# fullerton.net
KiCad netlist of a schematic drawn in EAGLE
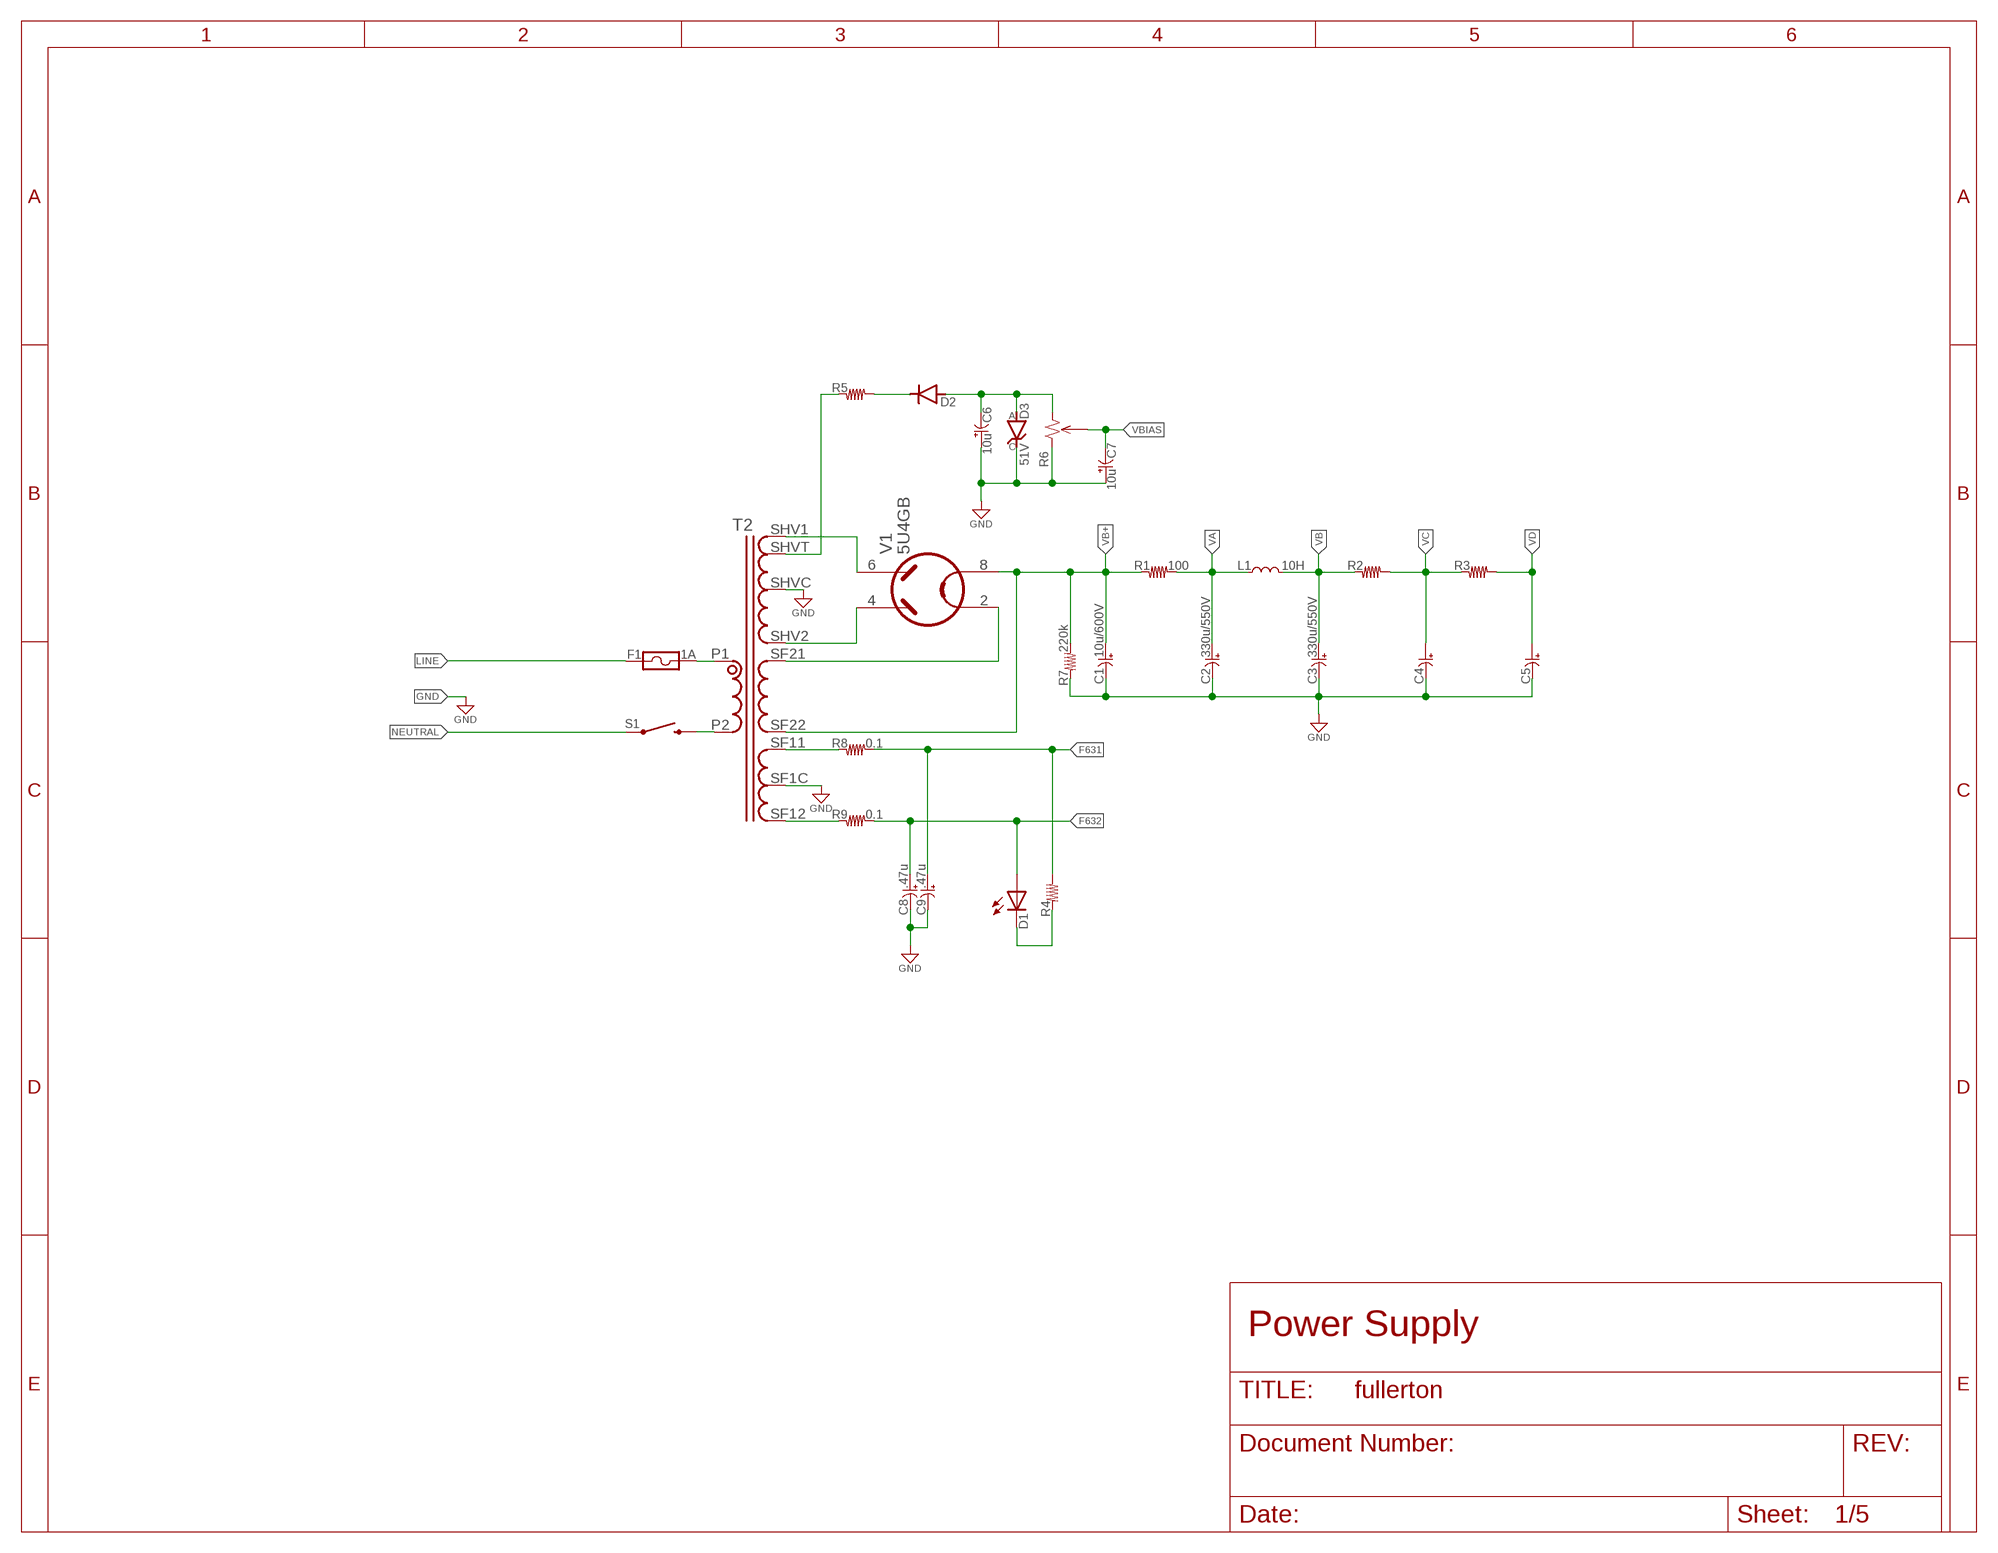
[diagram p0: schematic, sheet 1]
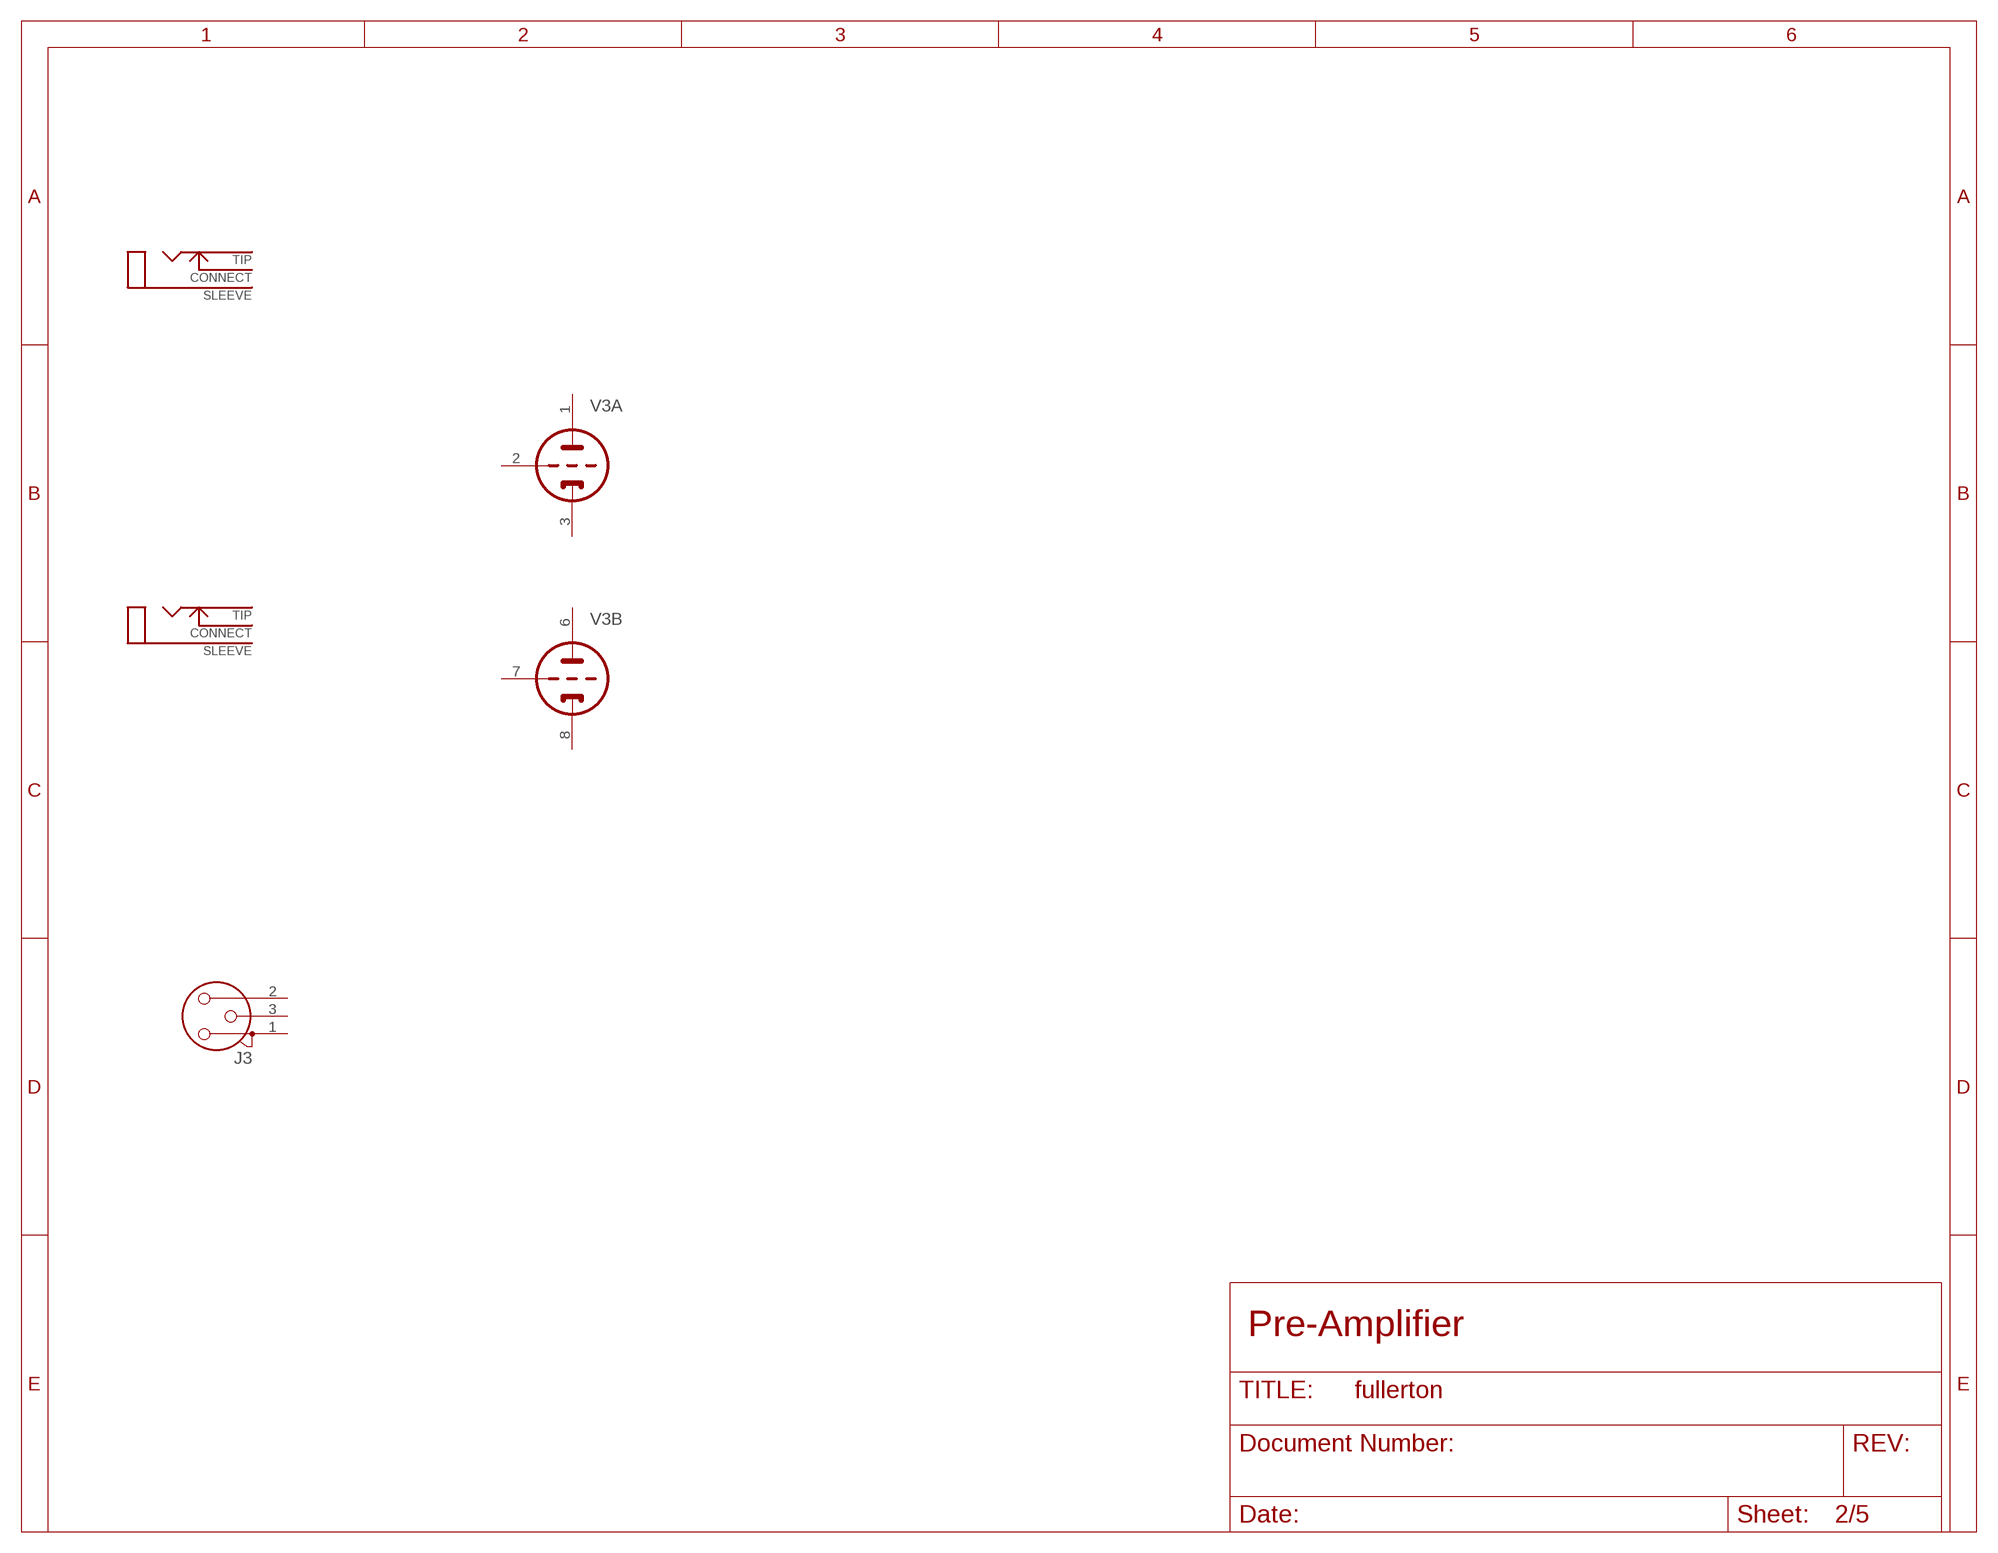
[diagram p1: schematic, sheet 2]
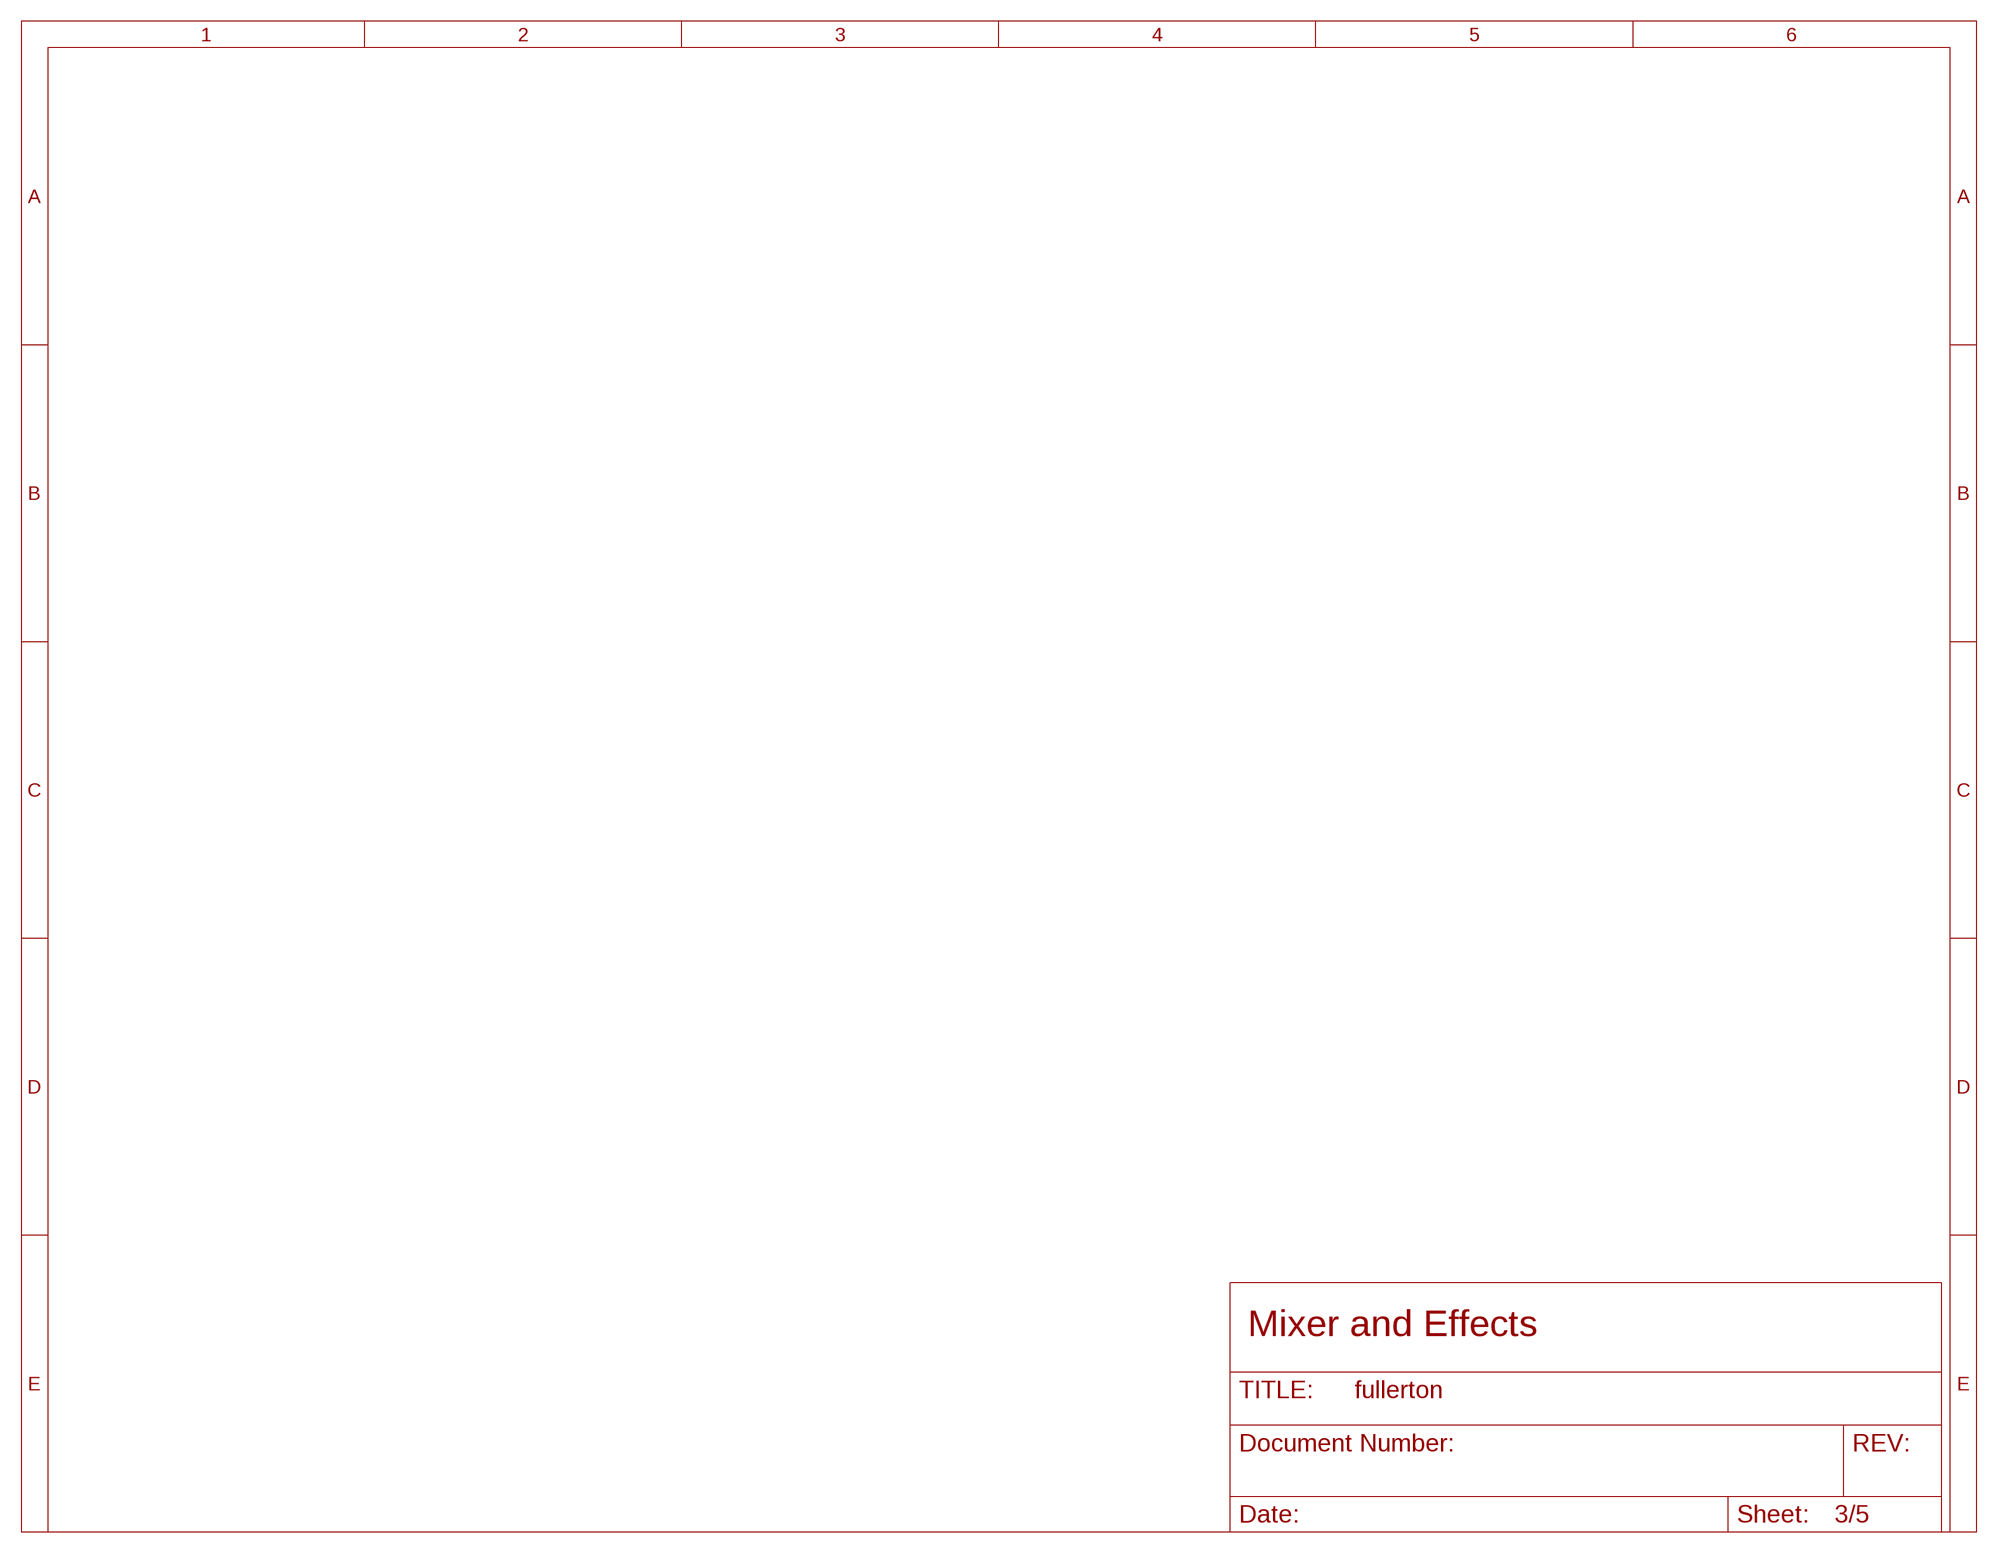
[diagram p2: schematic, sheet 3]
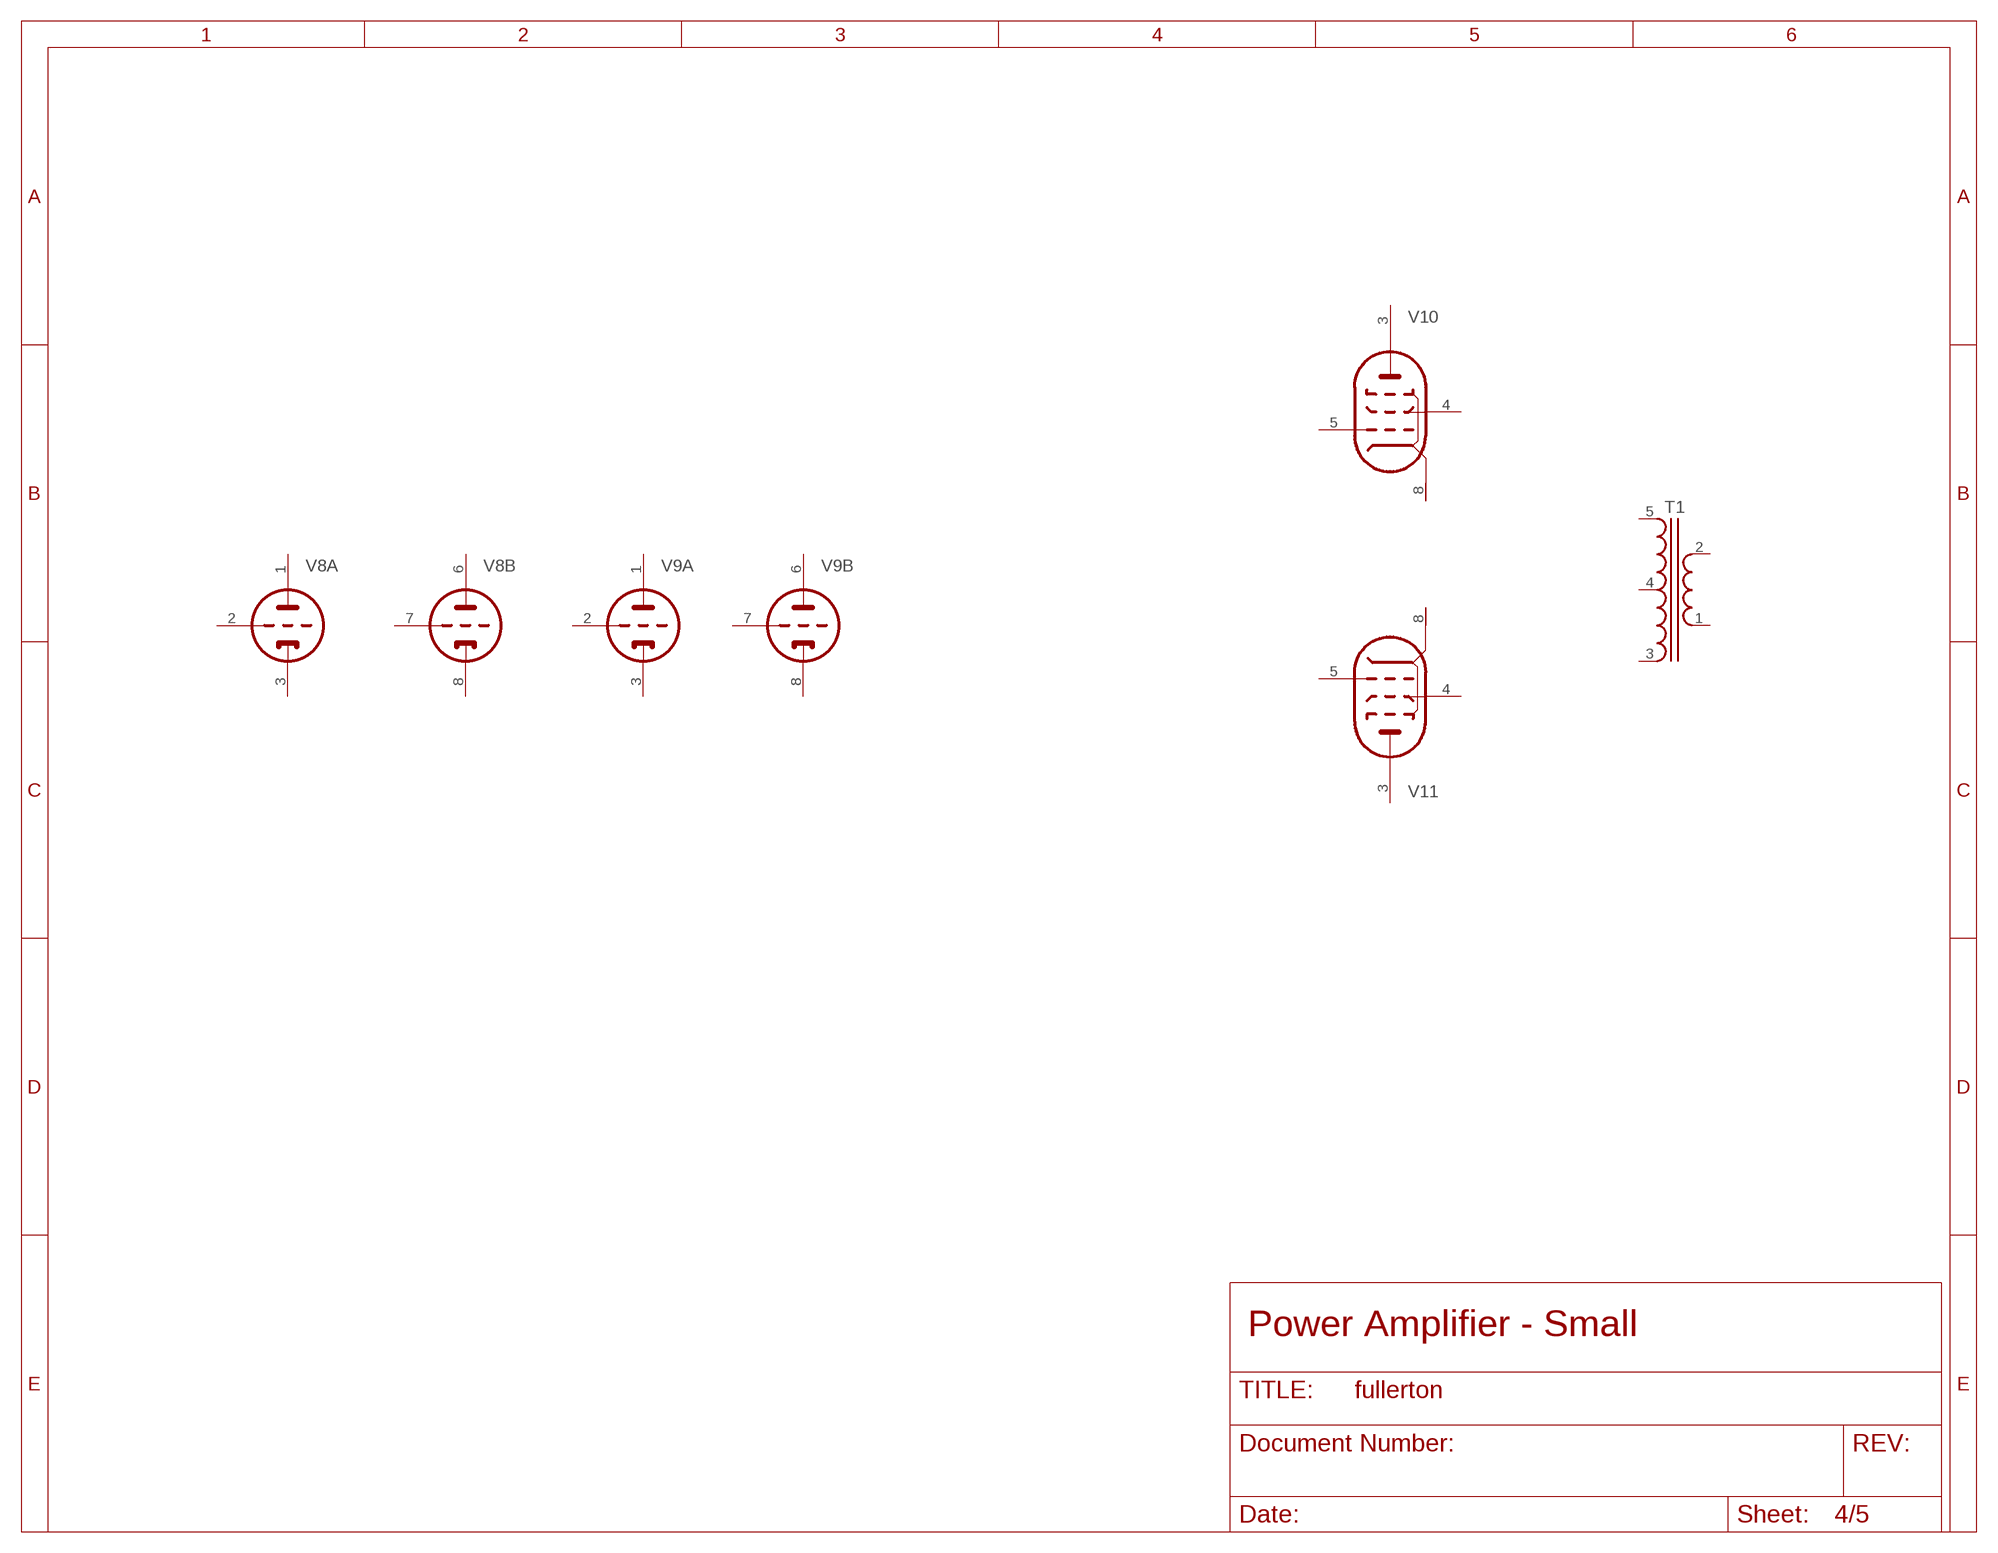
[diagram p3: schematic, sheet 4]
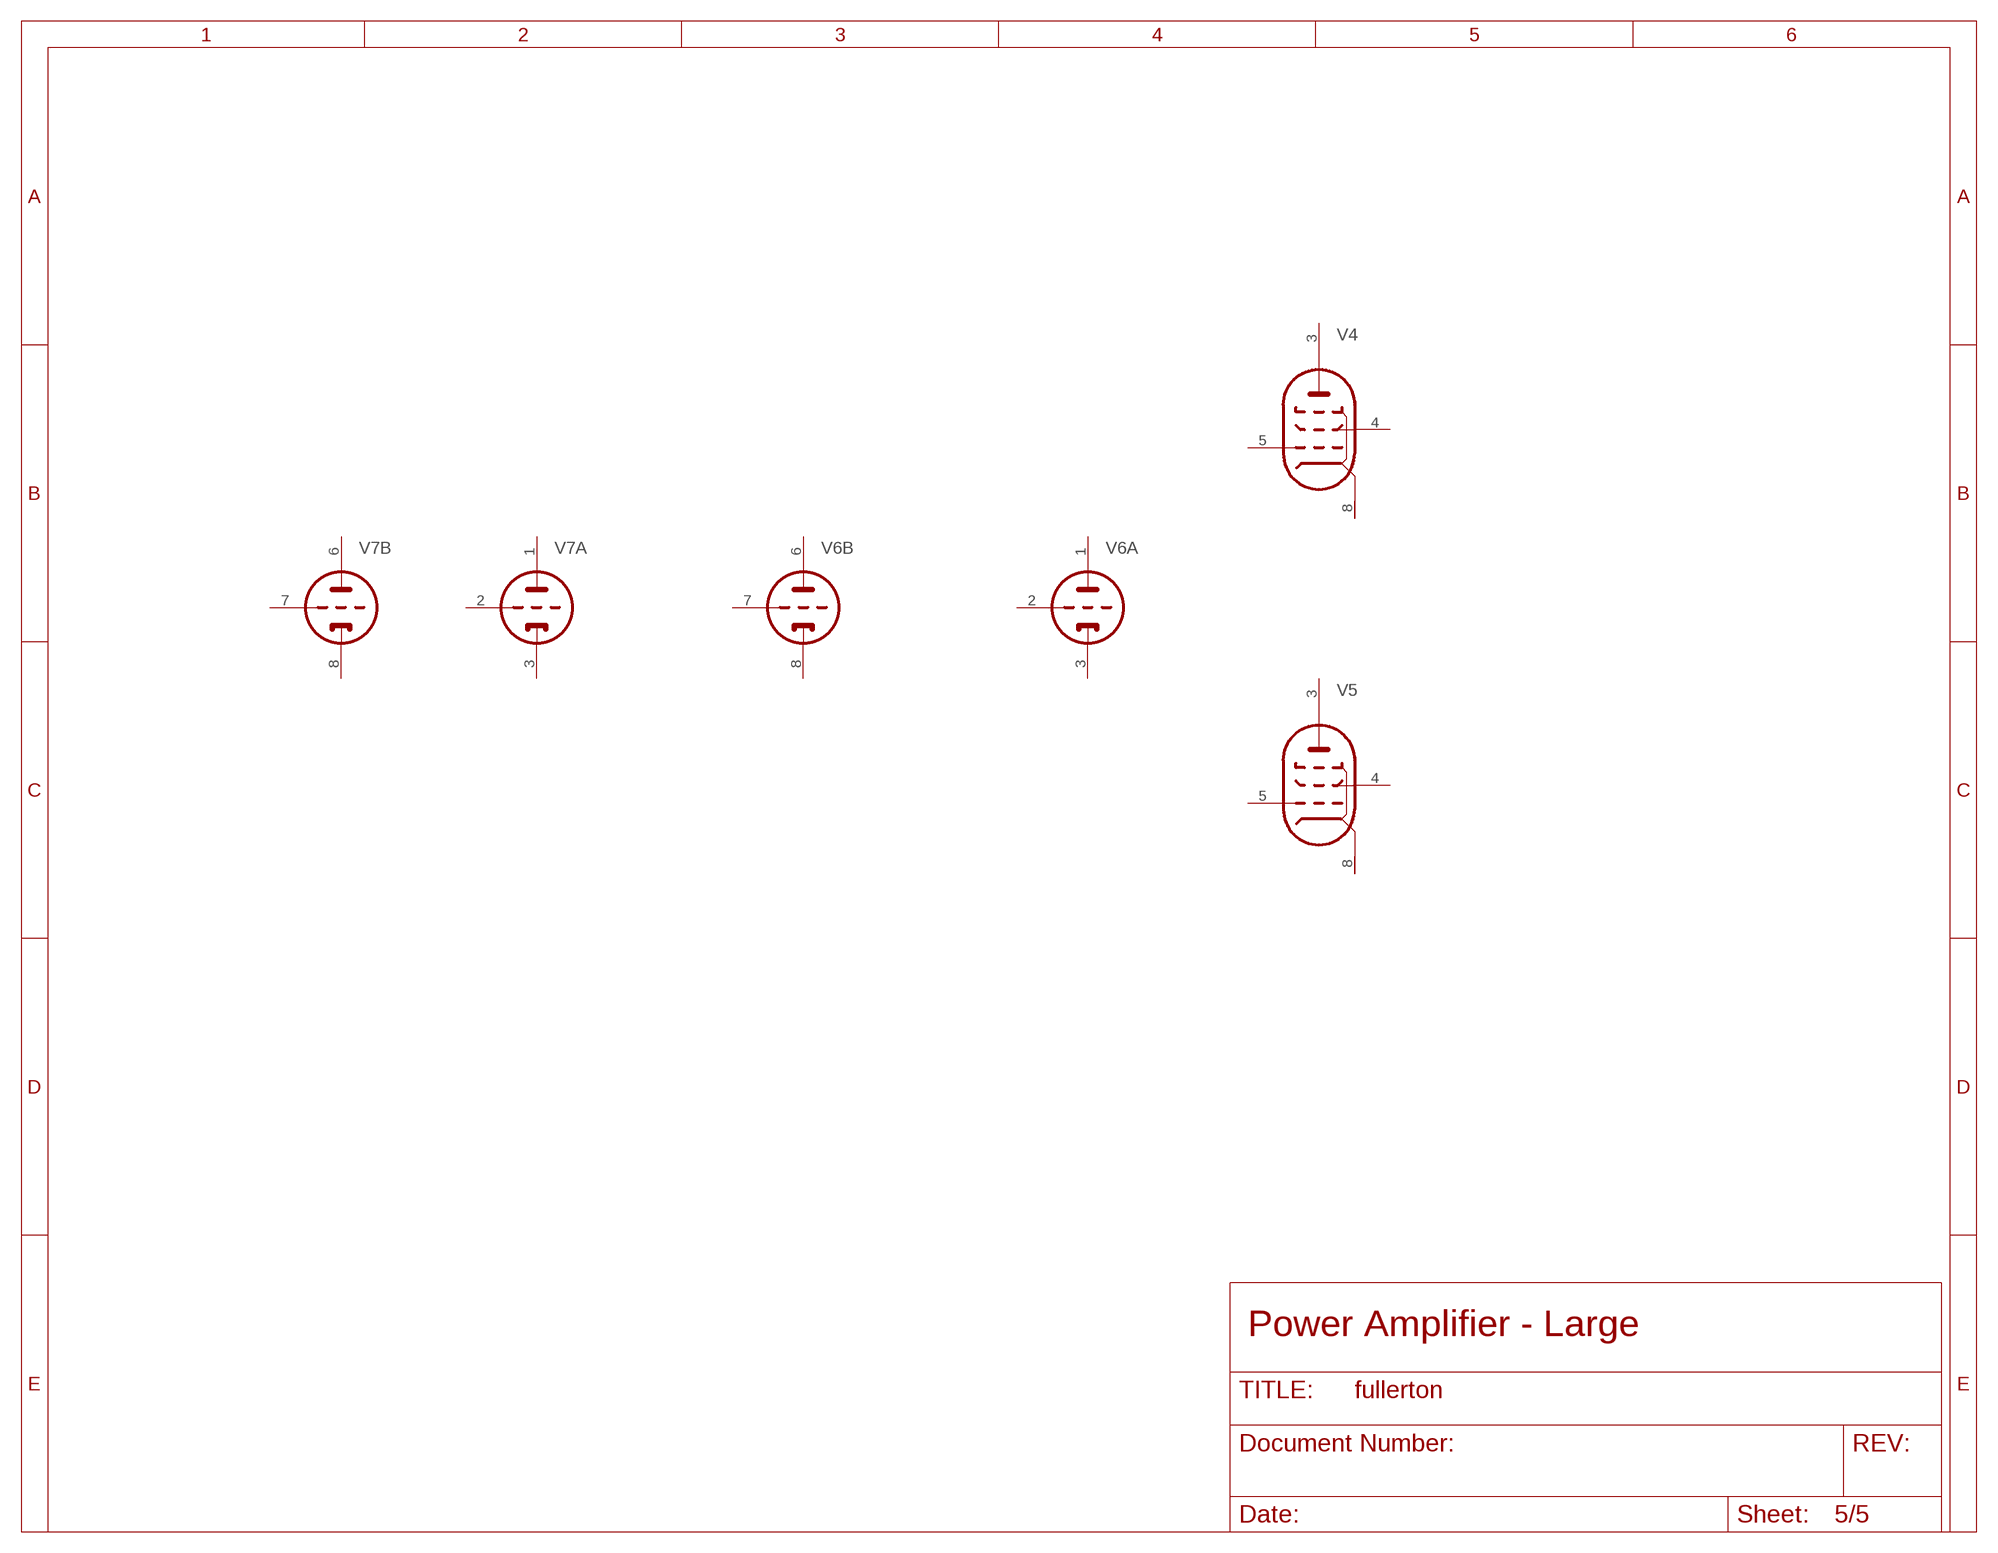
[diagram p4: schematic, sheet 5]

(export (version "E")
  (design (tool "Eeschema 10.0.6"))
  (components
    (comp (ref "J1")
      (value "CONN-JACK-1/4\"")
      (footprint "eagle-import:CONN-.100-3")
      (libsource (lib "eagle-import") (part "CONN-JACK-1/4{dblquote}"))
    )
    (comp (ref "J2")
      (value "CONN-JACK-1/4\"")
      (footprint "eagle-import:CONN-.100-3")
      (libsource (lib "eagle-import") (part "CONN-JACK-1/4{dblquote}"))
    )
    (comp (ref "J3")
      (value "CONN-JACK-XLR-3")
      (footprint "eagle-import:CONN-.100-3")
      (libsource (lib "eagle-import") (part "CONN-JACK-XLR-3"))
    )
    (comp (ref "V3")
      (value "12AT7-P")
      (footprint "eagle-import:NOVAL")
      (libsource (lib "eagle-import") (part "12AT7-P"))
    )
    (comp (ref "V4")
      (value "6L6GC-P")
      (footprint "eagle-import:OKTAL")
      (libsource (lib "eagle-import") (part "6L6GC-P"))
    )
    (comp (ref "V5")
      (value "6L6GC-P")
      (footprint "eagle-import:OKTAL")
      (libsource (lib "eagle-import") (part "6L6GC-P"))
    )
    (comp (ref "V6")
      (value "12AT7-P")
      (footprint "eagle-import:NOVAL")
      (libsource (lib "eagle-import") (part "12AT7-P"))
    )
    (comp (ref "V7")
      (value "12AT7-P")
      (footprint "eagle-import:NOVAL")
      (libsource (lib "eagle-import") (part "12AT7-P"))
    )
    (comp (ref "T1")
      (value "TRANSFORMER-3-2")
      (footprint "eagle-import:CONN-.100-5")
      (libsource (lib "eagle-import") (part "TRANSFORMER-3-2"))
    )
    (comp (ref "V8")
      (value "12AT7-P")
      (footprint "eagle-import:NOVAL")
      (libsource (lib "eagle-import") (part "12AT7-P"))
    )
    (comp (ref "V9")
      (value "12AT7-P")
      (footprint "eagle-import:NOVAL")
      (libsource (lib "eagle-import") (part "12AT7-P"))
    )
    (comp (ref "V10")
      (value "6K6GT-P")
      (footprint "eagle-import:OKTAL")
      (libsource (lib "eagle-import") (part "6K6GT-P"))
    )
    (comp (ref "V11")
      (value "6K6GT-P")
      (footprint "eagle-import:OKTAL")
      (libsource (lib "eagle-import") (part "6K6GT-P"))
    )
    (comp (ref "C1")
      (value "10u/600V")
      (footprint "eagle-import:C1210")
      (libsource (lib "eagle-import") (part "C-USC1210"))
    )
    (comp (ref "C2")
      (value "330u/550V")
      (footprint "eagle-import:C1210")
      (libsource (lib "eagle-import") (part "C-USC1210"))
    )
    (comp (ref "C3")
      (value "330u/550V")
      (footprint "eagle-import:C1210")
      (libsource (lib "eagle-import") (part "C-USC1210"))
    )
    (comp (ref "C4")
      (value "C-USC1210")
      (footprint "eagle-import:C1210")
      (libsource (lib "eagle-import") (part "C-USC1210"))
    )
    (comp (ref "C5")
      (value "C-USC1210")
      (footprint "eagle-import:C1210")
      (libsource (lib "eagle-import") (part "C-USC1210"))
    )
    (comp (ref "C6")
      (value "10u")
      (footprint "eagle-import:C1210")
      (libsource (lib "eagle-import") (part "C-USC1210"))
    )
    (comp (ref "C7")
      (value "10u")
      (footprint "eagle-import:C1210")
      (libsource (lib "eagle-import") (part "C-USC1210"))
    )
    (comp (ref "C8")
      (value ".47u")
      (footprint "eagle-import:C1210")
      (libsource (lib "eagle-import") (part "C-USC1210"))
    )
    (comp (ref "C9")
      (value ".47u")
      (footprint "eagle-import:C1210")
      (libsource (lib "eagle-import") (part "C-USC1210"))
    )
    (comp (ref "D1")
      (value "LED-3MM-0.1")
      (footprint "eagle-import:LED3MM")
      (libsource (lib "eagle-import") (part "LED-3MM-0.1"))
    )
    (comp (ref "D2")
      (value "DIODE-1N4148")
      (footprint "eagle-import:DO-35")
      (libsource (lib "eagle-import") (part "DIODE-1N4148"))
    )
    (comp (ref "D3")
      (value "51V")
      (footprint "eagle-import:SOD-323")
      (libsource (lib "eagle-import") (part "ZENER-SOD323"))
    )
    (comp (ref "F1")
      (value "1A")
      (footprint "eagle-import:3557-2")
      (libsource (lib "eagle-import") (part "FUSE-HOLDER-3557-2"))
    )
    (comp (ref "L1")
      (value "10H")
      (footprint "eagle-import:DR127")
      (libsource (lib "eagle-import") (part "INDUCTOR-DR127"))
    )
    (comp (ref "R1")
      (value "100")
      (footprint "eagle-import:R1206")
      (libsource (lib "eagle-import") (part "R-US_R1206"))
    )
    (comp (ref "R2")
      (value "R-US_R1206")
      (footprint "eagle-import:R1206")
      (libsource (lib "eagle-import") (part "R-US_R1206"))
    )
    (comp (ref "R3")
      (value "R-US_R1206")
      (footprint "eagle-import:R1206")
      (libsource (lib "eagle-import") (part "R-US_R1206"))
    )
    (comp (ref "R4")
      (value "R-US_R1206")
      (footprint "eagle-import:R1206")
      (libsource (lib "eagle-import") (part "R-US_R1206"))
    )
    (comp (ref "R5")
      (value "R-US_R1206")
      (footprint "eagle-import:R1206")
      (libsource (lib "eagle-import") (part "R-US_R1206"))
    )
    (comp (ref "R6")
      (value "POTENTIOMETER")
      (footprint "eagle-import:CONN-.100-3")
      (libsource (lib "eagle-import") (part "POTENTIOMETER"))
    )
    (comp (ref "R7")
      (value "220k")
      (footprint "eagle-import:R1206")
      (libsource (lib "eagle-import") (part "R-US_R1206"))
    )
    (comp (ref "R8")
      (value "0.1")
      (footprint "eagle-import:R1206")
      (libsource (lib "eagle-import") (part "R-US_R1206"))
    )
    (comp (ref "R9")
      (value "0.1")
      (footprint "eagle-import:R1206")
      (libsource (lib "eagle-import") (part "R-US_R1206"))
    )
    (comp (ref "S1")
      (value "SWITCH-PANEL-SPST")
      (footprint "eagle-import:CONN-.100-2")
      (libsource (lib "eagle-import") (part "SWITCH-PANEL-SPST"))
    )
    (comp (ref "T2")
      (value "TRANSFORMER-1-3C")
      (footprint "eagle-import:TRANSFORMER-1-3C")
      (libsource (lib "eagle-import") (part "TRANSFORMER-1-3C"))
    )
    (comp (ref "V1")
      (value "5U4GB")
      (footprint "eagle-import:OKTAL")
      (libsource (lib "eagle-import") (part "5U4GB"))
    )
  )
  (nets
    (net (code "1") (name "F631") (class "Default")
      (node (ref "C9") (pin "1") (pinfunction "1_1") (pintype "passive"))
      (node (ref "R4") (pin "2") (pinfunction "2_2") (pintype "passive"))
      (node (ref "R8") (pin "2") (pinfunction "2_2") (pintype "passive"))
    )
    (net (code "2") (name "F632") (class "Default")
      (node (ref "C8") (pin "1") (pinfunction "1_1") (pintype "passive"))
      (node (ref "D1") (pin "A") (pinfunction "A_A") (pintype "passive"))
      (node (ref "R9") (pin "2") (pinfunction "2_2") (pintype "passive"))
    )
    (net (code "3") (name "GND") (class "Default")
      (node (ref "C1") (pin "2") (pinfunction "2_2") (pintype "passive"))
      (node (ref "C2") (pin "2") (pinfunction "2_2") (pintype "passive"))
      (node (ref "C3") (pin "2") (pinfunction "2_2") (pintype "passive"))
      (node (ref "C4") (pin "2") (pinfunction "2_2") (pintype "passive"))
      (node (ref "C5") (pin "2") (pinfunction "2_2") (pintype "passive"))
      (node (ref "C6") (pin "1") (pinfunction "1_1") (pintype "passive"))
      (node (ref "C7") (pin "1") (pinfunction "1_1") (pintype "passive"))
      (node (ref "C8") (pin "2") (pinfunction "2_2") (pintype "passive"))
      (node (ref "C9") (pin "2") (pinfunction "2_2") (pintype "passive"))
      (node (ref "D3") (pin "C") (pinfunction "C_C") (pintype "bidirectional"))
      (node (ref "R6") (pin "1") (pinfunction "1_1") (pintype "passive"))
      (node (ref "R7") (pin "1") (pinfunction "1_1") (pintype "passive"))
      (node (ref "T2") (pin "SF1C") (pinfunction "SF1C_SF1C") (pintype "passive"))
      (node (ref "T2") (pin "SHVC") (pinfunction "SHVC_SHVC") (pintype "passive"))
    )
    (net (code "4") (name "LINE") (class "Default")
      (node (ref "F1") (pin "1@1") (pinfunction "P$1_1@1") (pintype "bidirectional"))
      (node (ref "F1") (pin "1@2") (pinfunction "P$1_1@2") (pintype "bidirectional"))
    )
    (net (code "5") (name "NEUTRAL") (class "Default")
      (node (ref "S1") (pin "1") (pinfunction "1_1") (pintype "passive"))
    )
    (net (code "6") (name "Net-(D1-PadC)") (class "Default")
      (node (ref "D1") (pin "C") (pinfunction "C_C") (pintype "passive"))
      (node (ref "R4") (pin "1") (pinfunction "1_1") (pintype "passive"))
    )
    (net (code "7") (name "Net-(D2-PadC)") (class "Default")
      (node (ref "D2") (pin "C") (pinfunction "C_C") (pintype "bidirectional"))
      (node (ref "R5") (pin "2") (pinfunction "2_2") (pintype "passive"))
    )
    (net (code "8") (name "Net-(F1-P$2-Pad2@1)") (class "Default")
      (node (ref "F1") (pin "2@1") (pinfunction "P$2_2@1") (pintype "bidirectional"))
      (node (ref "F1") (pin "2@2") (pinfunction "P$2_2@2") (pintype "bidirectional"))
      (node (ref "T2") (pin "P1") (pinfunction "P1_P1") (pintype "passive"))
    )
    (net (code "9") (name "Net-(R5-Pad1)") (class "Default")
      (node (ref "R5") (pin "1") (pinfunction "1_1") (pintype "passive"))
      (node (ref "T2") (pin "SHVT") (pinfunction "SHVT_SHVT") (pintype "passive"))
    )
    (net (code "10") (name "Net-(R6-2)") (class "Default")
      (node (ref "C6") (pin "2") (pinfunction "2_2") (pintype "passive"))
      (node (ref "D2") (pin "A") (pinfunction "A_A") (pintype "bidirectional"))
      (node (ref "D3") (pin "A") (pinfunction "A_A") (pintype "bidirectional"))
      (node (ref "R6") (pin "3") (pinfunction "2_3") (pintype "passive"))
    )
    (net (code "11") (name "Net-(R8-Pad1)") (class "Default")
      (node (ref "R8") (pin "1") (pinfunction "1_1") (pintype "passive"))
      (node (ref "T2") (pin "SF11") (pinfunction "SF11_SF11") (pintype "passive"))
    )
    (net (code "12") (name "Net-(R9-Pad1)") (class "Default")
      (node (ref "R9") (pin "1") (pinfunction "1_1") (pintype "passive"))
      (node (ref "T2") (pin "SF12") (pinfunction "SF12_SF12") (pintype "passive"))
    )
    (net (code "13") (name "Net-(S1-Pad2)") (class "Default")
      (node (ref "S1") (pin "2") (pinfunction "2_2") (pintype "passive"))
      (node (ref "T2") (pin "P2") (pinfunction "P2_P2") (pintype "passive"))
    )
    (net (code "14") (name "Net-(V1-A1)") (class "Default")
      (node (ref "T2") (pin "SHV2") (pinfunction "SHV2_SHV2") (pintype "passive"))
      (node (ref "V1") (pin "4") (pinfunction "A1_4") (pintype "passive"))
    )
    (net (code "15") (name "Net-(V1-A2)") (class "Default")
      (node (ref "T2") (pin "SHV1") (pinfunction "SHV1_SHV1") (pintype "passive"))
      (node (ref "V1") (pin "6") (pinfunction "A2_6") (pintype "passive"))
    )
    (net (code "16") (name "Net-(V1-H1)") (class "Default")
      (node (ref "T2") (pin "SF21") (pinfunction "SF21_SF21") (pintype "passive"))
      (node (ref "V1") (pin "2") (pinfunction "H1_2") (pintype "passive"))
    )
    (net (code "17") (name "VA") (class "Default")
      (node (ref "C2") (pin "1") (pinfunction "1_1") (pintype "passive"))
      (node (ref "L1") (pin "2") (pinfunction "P$2_2") (pintype "passive"))
      (node (ref "R1") (pin "2") (pinfunction "2_2") (pintype "passive"))
    )
    (net (code "18") (name "VB") (class "Default")
      (node (ref "C3") (pin "1") (pinfunction "1_1") (pintype "passive"))
      (node (ref "L1") (pin "1") (pinfunction "P$1_1") (pintype "passive"))
      (node (ref "R2") (pin "1") (pinfunction "1_1") (pintype "passive"))
    )
    (net (code "19") (name "VB+") (class "Default")
      (node (ref "C1") (pin "1") (pinfunction "1_1") (pintype "passive"))
      (node (ref "R1") (pin "1") (pinfunction "1_1") (pintype "passive"))
      (node (ref "R7") (pin "2") (pinfunction "2_2") (pintype "passive"))
      (node (ref "T2") (pin "SF22") (pinfunction "SF22_SF22") (pintype "passive"))
      (node (ref "V1") (pin "8") (pinfunction "H2_8") (pintype "passive"))
    )
    (net (code "20") (name "VBIAS") (class "Default")
      (node (ref "C7") (pin "2") (pinfunction "2_2") (pintype "passive"))
      (node (ref "R6") (pin "2") (pinfunction "W_2") (pintype "passive"))
    )
    (net (code "21") (name "VC") (class "Default")
      (node (ref "C4") (pin "1") (pinfunction "1_1") (pintype "passive"))
      (node (ref "R2") (pin "2") (pinfunction "2_2") (pintype "passive"))
      (node (ref "R3") (pin "1") (pinfunction "1_1") (pintype "passive"))
    )
    (net (code "22") (name "VD") (class "Default")
      (node (ref "C5") (pin "1") (pinfunction "1_1") (pintype "passive"))
      (node (ref "R3") (pin "2") (pinfunction "2_2") (pintype "passive"))
    )
    (net (code "23") (name "unconnected-(J1-CONNECT-Pad3)") (class "Default")
      (node (ref "J1") (pin "3") (pinfunction "CONNECT_3") (pintype "bidirectional"))
    )
    (net (code "24") (name "unconnected-(J1-SLEEVE-Pad1)") (class "Default")
      (node (ref "J1") (pin "1") (pinfunction "SLEEVE_1") (pintype "bidirectional"))
    )
    (net (code "25") (name "unconnected-(J1-TIP-Pad2)") (class "Default")
      (node (ref "J1") (pin "2") (pinfunction "TIP_2") (pintype "bidirectional"))
    )
    (net (code "26") (name "unconnected-(J2-CONNECT-Pad3)") (class "Default")
      (node (ref "J2") (pin "3") (pinfunction "CONNECT_3") (pintype "bidirectional"))
    )
    (net (code "27") (name "unconnected-(J2-SLEEVE-Pad1)") (class "Default")
      (node (ref "J2") (pin "1") (pinfunction "SLEEVE_1") (pintype "bidirectional"))
    )
    (net (code "28") (name "unconnected-(J2-TIP-Pad2)") (class "Default")
      (node (ref "J2") (pin "2") (pinfunction "TIP_2") (pintype "bidirectional"))
    )
    (net (code "29") (name "unconnected-(J3-Pad1)") (class "Default")
      (node (ref "J3") (pin "1") (pinfunction "1_1") (pintype "passive"))
    )
    (net (code "30") (name "unconnected-(J3-Pad2)") (class "Default")
      (node (ref "J3") (pin "2") (pinfunction "2_2") (pintype "passive"))
    )
    (net (code "31") (name "unconnected-(J3-Pad3)") (class "Default")
      (node (ref "J3") (pin "3") (pinfunction "3_3") (pintype "passive"))
    )
    (net (code "32") (name "unconnected-(T1-P1-Pad3)") (class "Default")
      (node (ref "T1") (pin "3") (pinfunction "P1_3") (pintype "passive"))
    )
    (net (code "33") (name "unconnected-(T1-P2-Pad5)") (class "Default")
      (node (ref "T1") (pin "5") (pinfunction "P2_5") (pintype "passive"))
    )
    (net (code "34") (name "unconnected-(T1-PCT-Pad4)") (class "Default")
      (node (ref "T1") (pin "4") (pinfunction "PCT_4") (pintype "passive"))
    )
    (net (code "35") (name "unconnected-(T1-S1-Pad1)") (class "Default")
      (node (ref "T1") (pin "1") (pinfunction "S1_1") (pintype "passive"))
    )
    (net (code "36") (name "unconnected-(T1-S2-Pad2)") (class "Default")
      (node (ref "T1") (pin "2") (pinfunction "S2_2") (pintype "passive"))
    )
    (net (code "37") (name "unconnected-(V3B-TA-Pad1)") (class "Default")
      (node (ref "V3") (pin "1") (pinfunction "TA_1") (pintype "passive"))
    )
    (net (code "38") (name "unconnected-(V3B-TG-Pad2)") (class "Default")
      (node (ref "V3") (pin "2") (pinfunction "TG_2") (pintype "passive"))
    )
    (net (code "39") (name "unconnected-(V3B-TK-Pad3)") (class "Default")
      (node (ref "V3") (pin "3") (pinfunction "TK_3") (pintype "passive"))
    )
    (net (code "40") (name "unconnected-(V3C-TA-Pad6)") (class "Default")
      (node (ref "V3") (pin "6") (pinfunction "TA_6") (pintype "passive"))
    )
    (net (code "41") (name "unconnected-(V3C-TG-Pad7)") (class "Default")
      (node (ref "V3") (pin "7") (pinfunction "TG_7") (pintype "passive"))
    )
    (net (code "42") (name "unconnected-(V3C-TK-Pad8)") (class "Default")
      (node (ref "V3") (pin "8") (pinfunction "TK_8") (pintype "passive"))
    )
    (net (code "43") (name "unconnected-(V4B-PA-Pad3)") (class "Default")
      (node (ref "V4") (pin "3") (pinfunction "PA_3") (pintype "passive"))
    )
    (net (code "44") (name "unconnected-(V4B-PG-Pad5)") (class "Default")
      (node (ref "V4") (pin "5") (pinfunction "PG_5") (pintype "passive"))
    )
    (net (code "45") (name "unconnected-(V4B-PK-Pad8)") (class "Default")
      (node (ref "V4") (pin "8") (pinfunction "PK_8") (pintype "passive"))
    )
    (net (code "46") (name "unconnected-(V4B-PSG-Pad4)") (class "Default")
      (node (ref "V4") (pin "4") (pinfunction "PSG_4") (pintype "passive"))
    )
    (net (code "47") (name "unconnected-(V5B-PA-Pad3)") (class "Default")
      (node (ref "V5") (pin "3") (pinfunction "PA_3") (pintype "passive"))
    )
    (net (code "48") (name "unconnected-(V5B-PG-Pad5)") (class "Default")
      (node (ref "V5") (pin "5") (pinfunction "PG_5") (pintype "passive"))
    )
    (net (code "49") (name "unconnected-(V5B-PK-Pad8)") (class "Default")
      (node (ref "V5") (pin "8") (pinfunction "PK_8") (pintype "passive"))
    )
    (net (code "50") (name "unconnected-(V5B-PSG-Pad4)") (class "Default")
      (node (ref "V5") (pin "4") (pinfunction "PSG_4") (pintype "passive"))
    )
    (net (code "51") (name "unconnected-(V6B-TA-Pad1)") (class "Default")
      (node (ref "V6") (pin "1") (pinfunction "TA_1") (pintype "passive"))
    )
    (net (code "52") (name "unconnected-(V6B-TG-Pad2)") (class "Default")
      (node (ref "V6") (pin "2") (pinfunction "TG_2") (pintype "passive"))
    )
    (net (code "53") (name "unconnected-(V6B-TK-Pad3)") (class "Default")
      (node (ref "V6") (pin "3") (pinfunction "TK_3") (pintype "passive"))
    )
    (net (code "54") (name "unconnected-(V6C-TA-Pad6)") (class "Default")
      (node (ref "V6") (pin "6") (pinfunction "TA_6") (pintype "passive"))
    )
    (net (code "55") (name "unconnected-(V6C-TG-Pad7)") (class "Default")
      (node (ref "V6") (pin "7") (pinfunction "TG_7") (pintype "passive"))
    )
    (net (code "56") (name "unconnected-(V6C-TK-Pad8)") (class "Default")
      (node (ref "V6") (pin "8") (pinfunction "TK_8") (pintype "passive"))
    )
    (net (code "57") (name "unconnected-(V7B-TA-Pad1)") (class "Default")
      (node (ref "V7") (pin "1") (pinfunction "TA_1") (pintype "passive"))
    )
    (net (code "58") (name "unconnected-(V7B-TG-Pad2)") (class "Default")
      (node (ref "V7") (pin "2") (pinfunction "TG_2") (pintype "passive"))
    )
    (net (code "59") (name "unconnected-(V7B-TK-Pad3)") (class "Default")
      (node (ref "V7") (pin "3") (pinfunction "TK_3") (pintype "passive"))
    )
    (net (code "60") (name "unconnected-(V7C-TA-Pad6)") (class "Default")
      (node (ref "V7") (pin "6") (pinfunction "TA_6") (pintype "passive"))
    )
    (net (code "61") (name "unconnected-(V7C-TG-Pad7)") (class "Default")
      (node (ref "V7") (pin "7") (pinfunction "TG_7") (pintype "passive"))
    )
    (net (code "62") (name "unconnected-(V7C-TK-Pad8)") (class "Default")
      (node (ref "V7") (pin "8") (pinfunction "TK_8") (pintype "passive"))
    )
    (net (code "63") (name "unconnected-(V8B-TA-Pad1)") (class "Default")
      (node (ref "V8") (pin "1") (pinfunction "TA_1") (pintype "passive"))
    )
    (net (code "64") (name "unconnected-(V8B-TG-Pad2)") (class "Default")
      (node (ref "V8") (pin "2") (pinfunction "TG_2") (pintype "passive"))
    )
    (net (code "65") (name "unconnected-(V8B-TK-Pad3)") (class "Default")
      (node (ref "V8") (pin "3") (pinfunction "TK_3") (pintype "passive"))
    )
    (net (code "66") (name "unconnected-(V8C-TA-Pad6)") (class "Default")
      (node (ref "V8") (pin "6") (pinfunction "TA_6") (pintype "passive"))
    )
    (net (code "67") (name "unconnected-(V8C-TG-Pad7)") (class "Default")
      (node (ref "V8") (pin "7") (pinfunction "TG_7") (pintype "passive"))
    )
    (net (code "68") (name "unconnected-(V8C-TK-Pad8)") (class "Default")
      (node (ref "V8") (pin "8") (pinfunction "TK_8") (pintype "passive"))
    )
    (net (code "69") (name "unconnected-(V9B-TA-Pad1)") (class "Default")
      (node (ref "V9") (pin "1") (pinfunction "TA_1") (pintype "passive"))
    )
    (net (code "70") (name "unconnected-(V9B-TG-Pad2)") (class "Default")
      (node (ref "V9") (pin "2") (pinfunction "TG_2") (pintype "passive"))
    )
    (net (code "71") (name "unconnected-(V9B-TK-Pad3)") (class "Default")
      (node (ref "V9") (pin "3") (pinfunction "TK_3") (pintype "passive"))
    )
    (net (code "72") (name "unconnected-(V9C-TA-Pad6)") (class "Default")
      (node (ref "V9") (pin "6") (pinfunction "TA_6") (pintype "passive"))
    )
    (net (code "73") (name "unconnected-(V9C-TG-Pad7)") (class "Default")
      (node (ref "V9") (pin "7") (pinfunction "TG_7") (pintype "passive"))
    )
    (net (code "74") (name "unconnected-(V9C-TK-Pad8)") (class "Default")
      (node (ref "V9") (pin "8") (pinfunction "TK_8") (pintype "passive"))
    )
    (net (code "75") (name "unconnected-(V10B-PA-Pad3)") (class "Default")
      (node (ref "V10") (pin "3") (pinfunction "PA_3") (pintype "passive"))
    )
    (net (code "76") (name "unconnected-(V10B-PG-Pad5)") (class "Default")
      (node (ref "V10") (pin "5") (pinfunction "PG_5") (pintype "passive"))
    )
    (net (code "77") (name "unconnected-(V10B-PK-Pad8)") (class "Default")
      (node (ref "V10") (pin "8") (pinfunction "PK_8") (pintype "passive"))
    )
    (net (code "78") (name "unconnected-(V10B-PSG-Pad4)") (class "Default")
      (node (ref "V10") (pin "4") (pinfunction "PSG_4") (pintype "passive"))
    )
    (net (code "79") (name "unconnected-(V11B-PA-Pad3)") (class "Default")
      (node (ref "V11") (pin "3") (pinfunction "PA_3") (pintype "passive"))
    )
    (net (code "80") (name "unconnected-(V11B-PG-Pad5)") (class "Default")
      (node (ref "V11") (pin "5") (pinfunction "PG_5") (pintype "passive"))
    )
    (net (code "81") (name "unconnected-(V11B-PK-Pad8)") (class "Default")
      (node (ref "V11") (pin "8") (pinfunction "PK_8") (pintype "passive"))
    )
    (net (code "82") (name "unconnected-(V11B-PSG-Pad4)") (class "Default")
      (node (ref "V11") (pin "4") (pinfunction "PSG_4") (pintype "passive"))
    )
  )
)
